# breakout.net
KiCad netlist of a schematic drawn in EAGLE
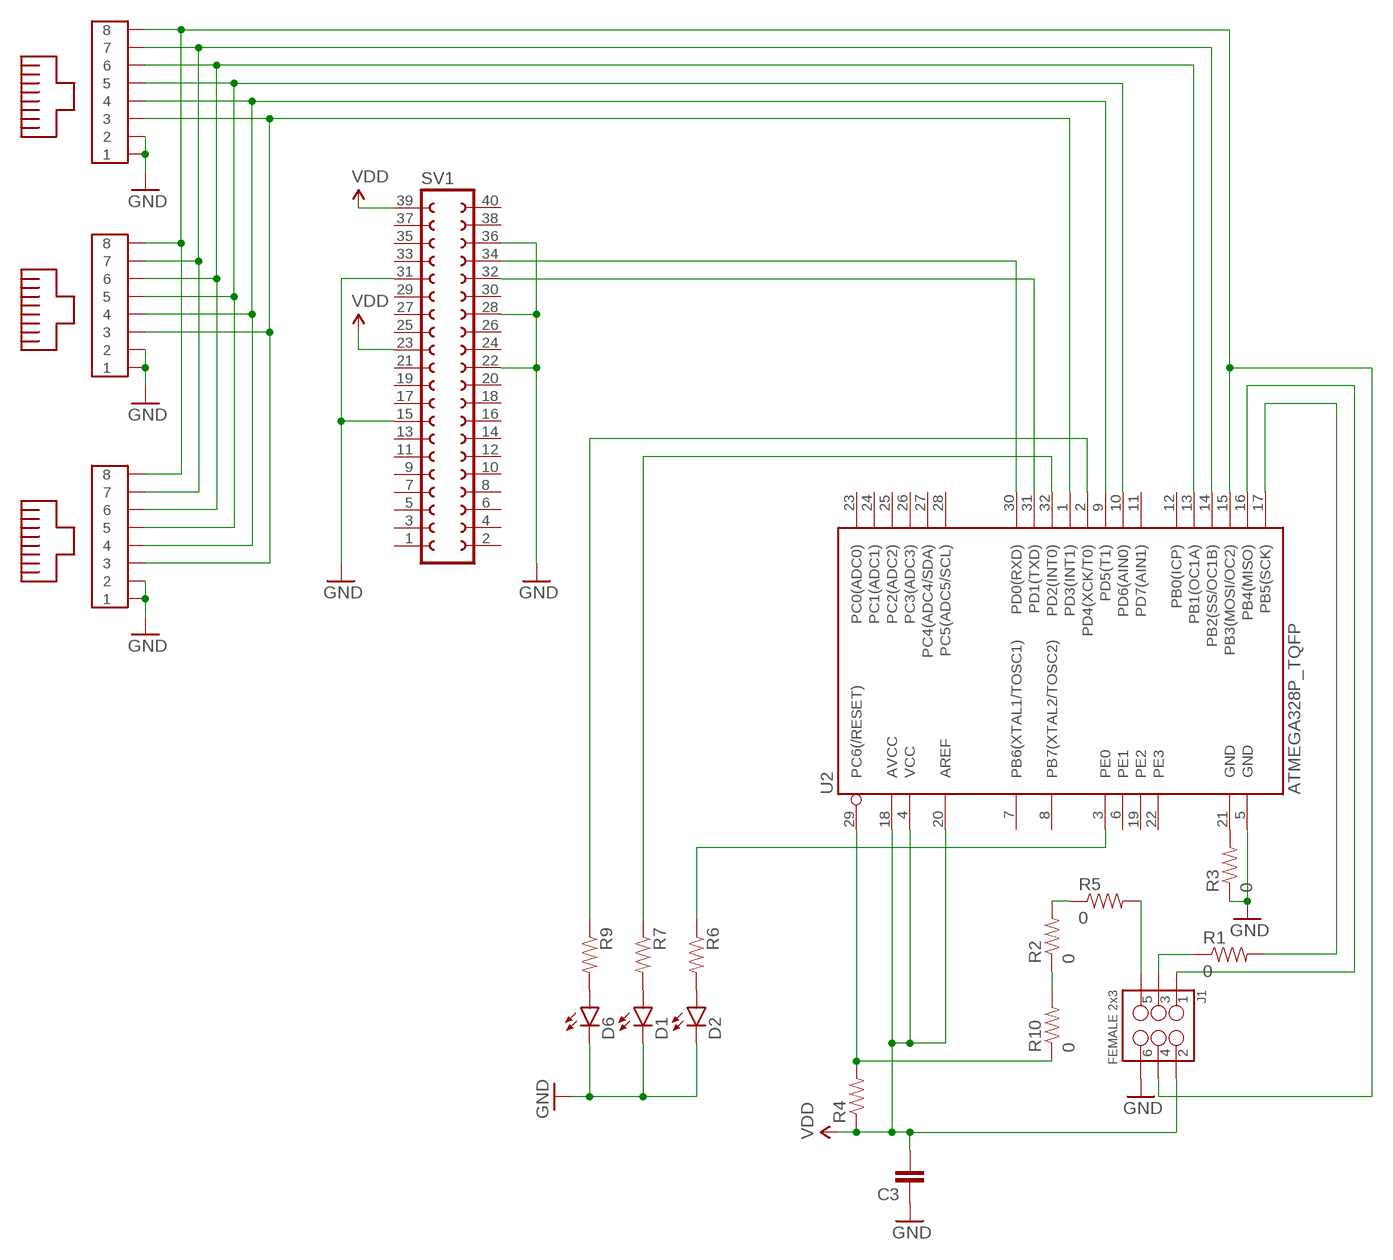
[diagram p0: schematic, sheet 1]

(export (version "E")
  (design (tool "Eeschema 10.0.6"))
  (components
    (comp (ref "C3")
      (value "CAP1206")
      (footprint "eagle-import:1206")
      (libsource (lib "eagle-import") (part "CAP1206"))
    )
    (comp (ref "D1")
      (value "LED0603")
      (footprint "eagle-import:LED-0603")
      (libsource (lib "eagle-import") (part "LED0603"))
    )
    (comp (ref "D2")
      (value "LED0603")
      (footprint "eagle-import:LED-0603")
      (libsource (lib "eagle-import") (part "LED0603"))
    )
    (comp (ref "D6")
      (value "LED0603")
      (footprint "eagle-import:LED-0603")
      (libsource (lib "eagle-import") (part "LED0603"))
    )
    (comp (ref "J1")
      (value "FEMALE 2x3")
      (footprint "eagle-import:2X3")
      (libsource (lib "eagle-import") (part "M03X2FEMALE"))
    )
    (comp (ref "R1")
      (value "0")
      (footprint "eagle-import:1206")
      (libsource (lib "eagle-import") (part "RESISTOR1206"))
    )
    (comp (ref "R2")
      (value "0")
      (footprint "eagle-import:1206")
      (libsource (lib "eagle-import") (part "RESISTOR1206"))
    )
    (comp (ref "R3")
      (value "0")
      (footprint "eagle-import:1206")
      (libsource (lib "eagle-import") (part "RESISTOR1206"))
    )
    (comp (ref "R4")
      (value "RESISTOR1206")
      (footprint "eagle-import:1206")
      (libsource (lib "eagle-import") (part "RESISTOR1206"))
    )
    (comp (ref "R5")
      (value "0")
      (footprint "eagle-import:1206")
      (libsource (lib "eagle-import") (part "RESISTOR1206"))
    )
    (comp (ref "R6")
      (value "RESISTOR1206")
      (footprint "eagle-import:1206")
      (libsource (lib "eagle-import") (part "RESISTOR1206"))
    )
    (comp (ref "R7")
      (value "RESISTOR1206")
      (footprint "eagle-import:1206")
      (libsource (lib "eagle-import") (part "RESISTOR1206"))
    )
    (comp (ref "R9")
      (value "RESISTOR1206")
      (footprint "eagle-import:1206")
      (libsource (lib "eagle-import") (part "RESISTOR1206"))
    )
    (comp (ref "R10")
      (value "0")
      (footprint "eagle-import:1206")
      (libsource (lib "eagle-import") (part "RESISTOR1206"))
    )
    (comp (ref "SV1")
      (value "FE20-2")
      (footprint "eagle-import:FE20-2")
      (libsource (lib "eagle-import") (part "FE20-2"))
    )
    (comp (ref "U$2")
      (value "MOLEX-RJ45-SMT")
      (footprint "eagle-import:MOLEX-RJ45-SMT")
      (libsource (lib "eagle-import") (part "MOLEX-RJ45-SMT"))
    )
    (comp (ref "U$3")
      (value "MOLEX-RJ45-SMT")
      (footprint "eagle-import:MOLEX-RJ45-SMT")
      (libsource (lib "eagle-import") (part "MOLEX-RJ45-SMT"))
    )
    (comp (ref "U$4")
      (value "MOLEX-RJ45-SMT")
      (footprint "eagle-import:MOLEX-RJ45-SMT")
      (libsource (lib "eagle-import") (part "MOLEX-RJ45-SMT"))
    )
    (comp (ref "U2")
      (value "ATMEGA328P_TQFP")
      (footprint "eagle-import:TQFP32-08")
      (libsource (lib "eagle-import") (part "ATMEGA328P_TQFP"))
    )
  )
  (nets
    (net (code "1") (name "GND") (class "Default")
      (node (ref "C3") (pin "1") (pinfunction "1_1") (pintype "passive"))
      (node (ref "D1") (pin "C") (pinfunction "C_C") (pintype "passive"))
      (node (ref "D2") (pin "C") (pinfunction "C_C") (pintype "passive"))
      (node (ref "D6") (pin "C") (pinfunction "C_C") (pintype "passive"))
      (node (ref "J1") (pin "6") (pinfunction "6_6") (pintype "bidirectional"))
      (node (ref "R3") (pin "1") (pinfunction "1_1") (pintype "passive"))
      (node (ref "SV1") (pin "15") (pinfunction "15_15") (pintype "passive"))
      (node (ref "SV1") (pin "22") (pinfunction "22_22") (pintype "passive"))
      (node (ref "SV1") (pin "28") (pinfunction "28_28") (pintype "passive"))
      (node (ref "SV1") (pin "31") (pinfunction "31_31") (pintype "passive"))
      (node (ref "SV1") (pin "36") (pinfunction "36_36") (pintype "passive"))
      (node (ref "U$2") (pin "1") (pinfunction "1_1") (pintype "bidirectional"))
      (node (ref "U$2") (pin "2") (pinfunction "2_2") (pintype "bidirectional"))
      (node (ref "U$3") (pin "1") (pinfunction "1_1") (pintype "bidirectional"))
      (node (ref "U$3") (pin "2") (pinfunction "2_2") (pintype "bidirectional"))
      (node (ref "U$4") (pin "1") (pinfunction "1_1") (pintype "bidirectional"))
      (node (ref "U$4") (pin "2") (pinfunction "2_2") (pintype "bidirectional"))
      (node (ref "U2") (pin "5") (pinfunction "GND_5") (pintype "bidirectional"))
    )
    (net (code "2") (name "Net-(D1-PadA)") (class "Default")
      (node (ref "D1") (pin "A") (pinfunction "A_A") (pintype "passive"))
      (node (ref "R7") (pin "2") (pinfunction "2_2") (pintype "passive"))
    )
    (net (code "3") (name "Net-(D2-PadA)") (class "Default")
      (node (ref "D2") (pin "A") (pinfunction "A_A") (pintype "passive"))
      (node (ref "R6") (pin "2") (pinfunction "2_2") (pintype "passive"))
    )
    (net (code "4") (name "Net-(D6-PadA)") (class "Default")
      (node (ref "D6") (pin "A") (pinfunction "A_A") (pintype "passive"))
      (node (ref "R9") (pin "2") (pinfunction "2_2") (pintype "passive"))
    )
    (net (code "5") (name "Net-(J1-Pad3)") (class "Default")
      (node (ref "J1") (pin "3") (pinfunction "3_3") (pintype "bidirectional"))
      (node (ref "R1") (pin "1") (pinfunction "1_1") (pintype "passive"))
    )
    (net (code "6") (name "Net-(J1-Pad5)") (class "Default")
      (node (ref "J1") (pin "5") (pinfunction "5_5") (pintype "bidirectional"))
      (node (ref "R5") (pin "2") (pinfunction "2_2") (pintype "passive"))
    )
    (net (code "7") (name "Net-(R2-Pad2)") (class "Default")
      (node (ref "R2") (pin "2") (pinfunction "2_2") (pintype "passive"))
      (node (ref "R5") (pin "1") (pinfunction "1_1") (pintype "passive"))
    )
    (net (code "8") (name "Net-(R3-Pad2)") (class "Default")
      (node (ref "R3") (pin "2") (pinfunction "2_2") (pintype "passive"))
      (node (ref "U2") (pin "21") (pinfunction "GND_21") (pintype "bidirectional"))
    )
    (net (code "9") (name "Net-(R10-Pad2)") (class "Default")
      (node (ref "R10") (pin "2") (pinfunction "2_2") (pintype "passive"))
      (node (ref "R2") (pin "1") (pinfunction "1_1") (pintype "passive"))
    )
    (net (code "10") (name "Net-(U2-PB1(OC1A))") (class "Default")
      (node (ref "U$2") (pin "6") (pinfunction "6_6") (pintype "bidirectional"))
      (node (ref "U$3") (pin "6") (pinfunction "6_6") (pintype "bidirectional"))
      (node (ref "U$4") (pin "6") (pinfunction "6_6") (pintype "bidirectional"))
      (node (ref "U2") (pin "13") (pinfunction "PB1(OC1A)_13") (pintype "bidirectional"))
    )
    (net (code "11") (name "Net-(U2-PB2(SS{slash}OC1B))") (class "Default")
      (node (ref "U$2") (pin "7") (pinfunction "7_7") (pintype "bidirectional"))
      (node (ref "U$3") (pin "7") (pinfunction "7_7") (pintype "bidirectional"))
      (node (ref "U$4") (pin "7") (pinfunction "7_7") (pintype "bidirectional"))
      (node (ref "U2") (pin "14") (pinfunction "PB2(SS/OC1B)_14") (pintype "bidirectional"))
    )
    (net (code "12") (name "Net-(U2-PB3(MOSI{slash}OC2))") (class "Default")
      (node (ref "J1") (pin "4") (pinfunction "4_4") (pintype "bidirectional"))
      (node (ref "U$2") (pin "8") (pinfunction "8_8") (pintype "bidirectional"))
      (node (ref "U$3") (pin "8") (pinfunction "8_8") (pintype "bidirectional"))
      (node (ref "U$4") (pin "8") (pinfunction "8_8") (pintype "bidirectional"))
      (node (ref "U2") (pin "15") (pinfunction "PB3(MOSI/OC2)_15") (pintype "bidirectional"))
    )
    (net (code "13") (name "Net-(U2-PB4(MISO))") (class "Default")
      (node (ref "J1") (pin "1") (pinfunction "1_1") (pintype "bidirectional"))
      (node (ref "U2") (pin "16") (pinfunction "PB4(MISO)_16") (pintype "bidirectional"))
    )
    (net (code "14") (name "Net-(U2-PB5(SCK))") (class "Default")
      (node (ref "R1") (pin "2") (pinfunction "2_2") (pintype "passive"))
      (node (ref "U2") (pin "17") (pinfunction "PB5(SCK)_17") (pintype "bidirectional"))
    )
    (net (code "15") (name "Net-(U2-PC6({slash}RESET))") (class "Default")
      (node (ref "R10") (pin "1") (pinfunction "1_1") (pintype "passive"))
      (node (ref "R4") (pin "2") (pinfunction "2_2") (pintype "passive"))
      (node (ref "U2") (pin "29") (pinfunction "PC6(/RESET)_29") (pintype "bidirectional"))
    )
    (net (code "16") (name "Net-(U2-PD0(RXD))") (class "Default")
      (node (ref "SV1") (pin "34") (pinfunction "34_34") (pintype "passive"))
      (node (ref "U2") (pin "30") (pinfunction "PD0(RXD)_30") (pintype "bidirectional"))
    )
    (net (code "17") (name "Net-(U2-PD1(TXD))") (class "Default")
      (node (ref "SV1") (pin "32") (pinfunction "32_32") (pintype "passive"))
      (node (ref "U2") (pin "31") (pinfunction "PD1(TXD)_31") (pintype "bidirectional"))
    )
    (net (code "18") (name "Net-(U2-PD2(INT0))") (class "Default")
      (node (ref "R7") (pin "1") (pinfunction "1_1") (pintype "passive"))
      (node (ref "U2") (pin "32") (pinfunction "PD2(INT0)_32") (pintype "bidirectional"))
    )
    (net (code "19") (name "Net-(U2-PD3(INT1))") (class "Default")
      (node (ref "U$2") (pin "3") (pinfunction "3_3") (pintype "bidirectional"))
      (node (ref "U$3") (pin "3") (pinfunction "3_3") (pintype "bidirectional"))
      (node (ref "U$4") (pin "3") (pinfunction "3_3") (pintype "bidirectional"))
      (node (ref "U2") (pin "1") (pinfunction "PD3(INT1)_1") (pintype "bidirectional"))
    )
    (net (code "20") (name "Net-(U2-PD4(XCK{slash}T0))") (class "Default")
      (node (ref "R9") (pin "1") (pinfunction "1_1") (pintype "passive"))
      (node (ref "U2") (pin "2") (pinfunction "PD4(XCK/T0)_2") (pintype "bidirectional"))
    )
    (net (code "21") (name "Net-(U2-PD5(T1))") (class "Default")
      (node (ref "U$2") (pin "4") (pinfunction "4_4") (pintype "bidirectional"))
      (node (ref "U$3") (pin "4") (pinfunction "4_4") (pintype "bidirectional"))
      (node (ref "U$4") (pin "4") (pinfunction "4_4") (pintype "bidirectional"))
      (node (ref "U2") (pin "9") (pinfunction "PD5(T1)_9") (pintype "bidirectional"))
    )
    (net (code "22") (name "Net-(U2-PD6(AIN0))") (class "Default")
      (node (ref "U$2") (pin "5") (pinfunction "5_5") (pintype "bidirectional"))
      (node (ref "U$3") (pin "5") (pinfunction "5_5") (pintype "bidirectional"))
      (node (ref "U$4") (pin "5") (pinfunction "5_5") (pintype "bidirectional"))
      (node (ref "U2") (pin "10") (pinfunction "PD6(AIN0)_10") (pintype "bidirectional"))
    )
    (net (code "23") (name "Net-(U2-PE0)") (class "Default")
      (node (ref "R6") (pin "1") (pinfunction "1_1") (pintype "passive"))
      (node (ref "U2") (pin "3") (pinfunction "PE0_3") (pintype "bidirectional"))
    )
    (net (code "24") (name "VDD") (class "Default")
      (node (ref "C3") (pin "2") (pinfunction "2_2") (pintype "passive"))
      (node (ref "J1") (pin "2") (pinfunction "2_2") (pintype "bidirectional"))
      (node (ref "R4") (pin "1") (pinfunction "1_1") (pintype "passive"))
      (node (ref "SV1") (pin "23") (pinfunction "23_23") (pintype "passive"))
      (node (ref "SV1") (pin "39") (pinfunction "39_39") (pintype "passive"))
      (node (ref "U2") (pin "18") (pinfunction "AVCC_18") (pintype "bidirectional"))
      (node (ref "U2") (pin "20") (pinfunction "AREF_20") (pintype "bidirectional"))
      (node (ref "U2") (pin "4") (pinfunction "VCC_4") (pintype "bidirectional"))
    )
    (net (code "25") (name "unconnected-(SV1-Pad1)") (class "Default")
      (node (ref "SV1") (pin "1") (pinfunction "1_1") (pintype "passive"))
    )
    (net (code "26") (name "unconnected-(SV1-Pad2)") (class "Default")
      (node (ref "SV1") (pin "2") (pinfunction "2_2") (pintype "passive"))
    )
    (net (code "27") (name "unconnected-(SV1-Pad3)") (class "Default")
      (node (ref "SV1") (pin "3") (pinfunction "3_3") (pintype "passive"))
    )
    (net (code "28") (name "unconnected-(SV1-Pad4)") (class "Default")
      (node (ref "SV1") (pin "4") (pinfunction "4_4") (pintype "passive"))
    )
    (net (code "29") (name "unconnected-(SV1-Pad5)") (class "Default")
      (node (ref "SV1") (pin "5") (pinfunction "5_5") (pintype "passive"))
    )
    (net (code "30") (name "unconnected-(SV1-Pad6)") (class "Default")
      (node (ref "SV1") (pin "6") (pinfunction "6_6") (pintype "passive"))
    )
    (net (code "31") (name "unconnected-(SV1-Pad7)") (class "Default")
      (node (ref "SV1") (pin "7") (pinfunction "7_7") (pintype "passive"))
    )
    (net (code "32") (name "unconnected-(SV1-Pad8)") (class "Default")
      (node (ref "SV1") (pin "8") (pinfunction "8_8") (pintype "passive"))
    )
    (net (code "33") (name "unconnected-(SV1-Pad9)") (class "Default")
      (node (ref "SV1") (pin "9") (pinfunction "9_9") (pintype "passive"))
    )
    (net (code "34") (name "unconnected-(SV1-Pad10)") (class "Default")
      (node (ref "SV1") (pin "10") (pinfunction "10_10") (pintype "passive"))
    )
    (net (code "35") (name "unconnected-(SV1-Pad11)") (class "Default")
      (node (ref "SV1") (pin "11") (pinfunction "11_11") (pintype "passive"))
    )
    (net (code "36") (name "unconnected-(SV1-Pad12)") (class "Default")
      (node (ref "SV1") (pin "12") (pinfunction "12_12") (pintype "passive"))
    )
    (net (code "37") (name "unconnected-(SV1-Pad13)") (class "Default")
      (node (ref "SV1") (pin "13") (pinfunction "13_13") (pintype "passive"))
    )
    (net (code "38") (name "unconnected-(SV1-Pad14)") (class "Default")
      (node (ref "SV1") (pin "14") (pinfunction "14_14") (pintype "passive"))
    )
    (net (code "39") (name "unconnected-(SV1-Pad16)") (class "Default")
      (node (ref "SV1") (pin "16") (pinfunction "16_16") (pintype "passive"))
    )
    (net (code "40") (name "unconnected-(SV1-Pad17)") (class "Default")
      (node (ref "SV1") (pin "17") (pinfunction "17_17") (pintype "passive"))
    )
    (net (code "41") (name "unconnected-(SV1-Pad18)") (class "Default")
      (node (ref "SV1") (pin "18") (pinfunction "18_18") (pintype "passive"))
    )
    (net (code "42") (name "unconnected-(SV1-Pad19)") (class "Default")
      (node (ref "SV1") (pin "19") (pinfunction "19_19") (pintype "passive"))
    )
    (net (code "43") (name "unconnected-(SV1-Pad20)") (class "Default")
      (node (ref "SV1") (pin "20") (pinfunction "20_20") (pintype "passive"))
    )
    (net (code "44") (name "unconnected-(SV1-Pad21)") (class "Default")
      (node (ref "SV1") (pin "21") (pinfunction "21_21") (pintype "passive"))
    )
    (net (code "45") (name "unconnected-(SV1-Pad24)") (class "Default")
      (node (ref "SV1") (pin "24") (pinfunction "24_24") (pintype "passive"))
    )
    (net (code "46") (name "unconnected-(SV1-Pad25)") (class "Default")
      (node (ref "SV1") (pin "25") (pinfunction "25_25") (pintype "passive"))
    )
    (net (code "47") (name "unconnected-(SV1-Pad26)") (class "Default")
      (node (ref "SV1") (pin "26") (pinfunction "26_26") (pintype "passive"))
    )
    (net (code "48") (name "unconnected-(SV1-Pad27)") (class "Default")
      (node (ref "SV1") (pin "27") (pinfunction "27_27") (pintype "passive"))
    )
    (net (code "49") (name "unconnected-(SV1-Pad29)") (class "Default")
      (node (ref "SV1") (pin "29") (pinfunction "29_29") (pintype "passive"))
    )
    (net (code "50") (name "unconnected-(SV1-Pad30)") (class "Default")
      (node (ref "SV1") (pin "30") (pinfunction "30_30") (pintype "passive"))
    )
    (net (code "51") (name "unconnected-(SV1-Pad33)") (class "Default")
      (node (ref "SV1") (pin "33") (pinfunction "33_33") (pintype "passive"))
    )
    (net (code "52") (name "unconnected-(SV1-Pad35)") (class "Default")
      (node (ref "SV1") (pin "35") (pinfunction "35_35") (pintype "passive"))
    )
    (net (code "53") (name "unconnected-(SV1-Pad37)") (class "Default")
      (node (ref "SV1") (pin "37") (pinfunction "37_37") (pintype "passive"))
    )
    (net (code "54") (name "unconnected-(SV1-Pad38)") (class "Default")
      (node (ref "SV1") (pin "38") (pinfunction "38_38") (pintype "passive"))
    )
    (net (code "55") (name "unconnected-(SV1-Pad40)") (class "Default")
      (node (ref "SV1") (pin "40") (pinfunction "40_40") (pintype "passive"))
    )
    (net (code "56") (name "unconnected-(U2-PB0(ICP)-Pad12)") (class "Default")
      (node (ref "U2") (pin "12") (pinfunction "PB0(ICP)_12") (pintype "bidirectional"))
    )
    (net (code "57") (name "unconnected-(U2-PB6(XTAL1{slash}TOSC1)-Pad7)") (class "Default")
      (node (ref "U2") (pin "7") (pinfunction "PB6(XTAL1/TOSC1)_7") (pintype "bidirectional"))
    )
    (net (code "58") (name "unconnected-(U2-PB7(XTAL2{slash}TOSC2)-Pad8)") (class "Default")
      (node (ref "U2") (pin "8") (pinfunction "PB7(XTAL2/TOSC2)_8") (pintype "bidirectional"))
    )
    (net (code "59") (name "unconnected-(U2-PC0(ADC0)-Pad23)") (class "Default")
      (node (ref "U2") (pin "23") (pinfunction "PC0(ADC0)_23") (pintype "bidirectional"))
    )
    (net (code "60") (name "unconnected-(U2-PC1(ADC1)-Pad24)") (class "Default")
      (node (ref "U2") (pin "24") (pinfunction "PC1(ADC1)_24") (pintype "bidirectional"))
    )
    (net (code "61") (name "unconnected-(U2-PC2(ADC2)-Pad25)") (class "Default")
      (node (ref "U2") (pin "25") (pinfunction "PC2(ADC2)_25") (pintype "bidirectional"))
    )
    (net (code "62") (name "unconnected-(U2-PC3(ADC3)-Pad26)") (class "Default")
      (node (ref "U2") (pin "26") (pinfunction "PC3(ADC3)_26") (pintype "bidirectional"))
    )
    (net (code "63") (name "unconnected-(U2-PC4(ADC4{slash}SDA)-Pad27)") (class "Default")
      (node (ref "U2") (pin "27") (pinfunction "PC4(ADC4/SDA)_27") (pintype "bidirectional"))
    )
    (net (code "64") (name "unconnected-(U2-PC5(ADC5{slash}SCL)-Pad28)") (class "Default")
      (node (ref "U2") (pin "28") (pinfunction "PC5(ADC5/SCL)_28") (pintype "bidirectional"))
    )
    (net (code "65") (name "unconnected-(U2-PD7(AIN1)-Pad11)") (class "Default")
      (node (ref "U2") (pin "11") (pinfunction "PD7(AIN1)_11") (pintype "bidirectional"))
    )
    (net (code "66") (name "unconnected-(U2-PE1-Pad6)") (class "Default")
      (node (ref "U2") (pin "6") (pinfunction "PE1_6") (pintype "bidirectional"))
    )
    (net (code "67") (name "unconnected-(U2-PE2-Pad19)") (class "Default")
      (node (ref "U2") (pin "19") (pinfunction "PE2_19") (pintype "bidirectional"))
    )
    (net (code "68") (name "unconnected-(U2-PE3-Pad22)") (class "Default")
      (node (ref "U2") (pin "22") (pinfunction "PE3_22") (pintype "bidirectional"))
    )
  )
)
